# v1.net
KiCad netlist of a schematic drawn in EAGLE
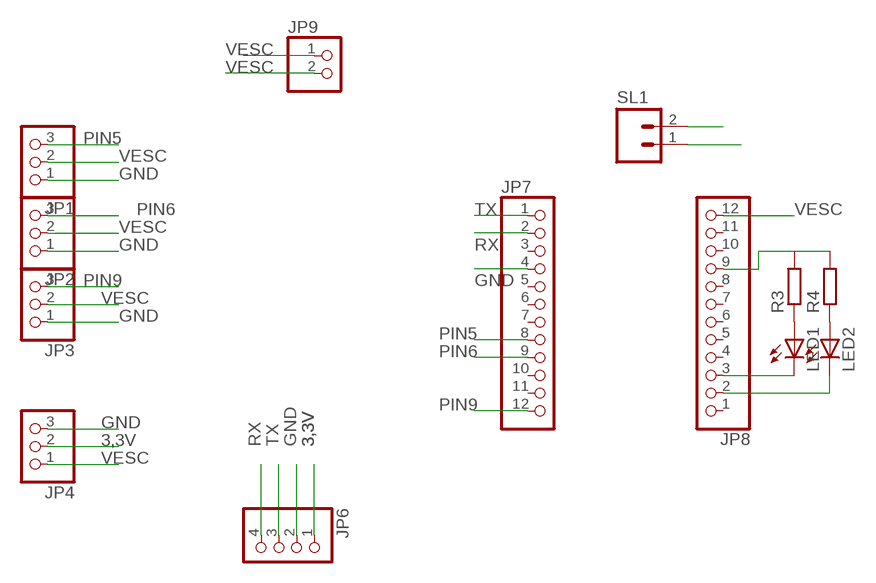
[diagram p0: schematic, sheet 1]

(export (version "E")
  (design (tool "Eeschema 10.0.6"))
  (components
    (comp (ref "JP1")
      (value "PINHD-1X3")
      (footprint "eagle-import:1X03")
      (libsource (lib "eagle-import") (part "PINHD-1X3"))
    )
    (comp (ref "JP2")
      (value "PINHD-1X3")
      (footprint "eagle-import:1X03")
      (libsource (lib "eagle-import") (part "PINHD-1X3"))
    )
    (comp (ref "JP3")
      (value "PINHD-1X3")
      (footprint "eagle-import:1X03")
      (libsource (lib "eagle-import") (part "PINHD-1X3"))
    )
    (comp (ref "JP4")
      (value "PINHD-1X3")
      (footprint "eagle-import:1X03")
      (libsource (lib "eagle-import") (part "PINHD-1X3"))
    )
    (comp (ref "JP6")
      (value "PINHD-1X4")
      (footprint "eagle-import:1X04")
      (libsource (lib "eagle-import") (part "PINHD-1X4"))
    )
    (comp (ref "JP7")
      (value "PINHD-1X12")
      (footprint "eagle-import:1X12")
      (libsource (lib "eagle-import") (part "PINHD-1X12"))
    )
    (comp (ref "JP8")
      (value "PINHD-1X12")
      (footprint "eagle-import:1X12")
      (libsource (lib "eagle-import") (part "PINHD-1X12"))
    )
    (comp (ref "JP9")
      (value "PINHD-1X2")
      (footprint "eagle-import:1X02")
      (libsource (lib "eagle-import") (part "PINHD-1X2"))
    )
    (comp (ref "LED1")
      (value "LED3MM")
      (footprint "eagle-import:LED3MM")
      (libsource (lib "eagle-import") (part "LED3MM"))
    )
    (comp (ref "LED2")
      (value "LED3MM")
      (footprint "eagle-import:LED3MM")
      (libsource (lib "eagle-import") (part "LED3MM"))
    )
    (comp (ref "R3")
      (value "R-EU_0207/7")
      (footprint "eagle-import:0207_7")
      (libsource (lib "eagle-import") (part "R-EU_0207/7"))
    )
    (comp (ref "R4")
      (value "R-EU_0207/7")
      (footprint "eagle-import:0207_7")
      (libsource (lib "eagle-import") (part "R-EU_0207/7"))
    )
    (comp (ref "SL1")
      (value "M02")
      (footprint "eagle-import:02P")
      (libsource (lib "eagle-import") (part "M02"))
    )
  )
  (nets
    (net (code "1") (name "/3,3V") (class "Default")
      (node (ref "JP4") (pin "2") (pinfunction "2_2") (pintype "passive"))
      (node (ref "JP6") (pin "1") (pinfunction "1_1") (pintype "passive"))
    )
    (net (code "2") (name "/GND") (class "Default")
      (node (ref "JP1") (pin "1") (pinfunction "1_1") (pintype "passive"))
      (node (ref "JP2") (pin "1") (pinfunction "1_1") (pintype "passive"))
      (node (ref "JP3") (pin "1") (pinfunction "1_1") (pintype "passive"))
      (node (ref "JP4") (pin "3") (pinfunction "3_3") (pintype "passive"))
      (node (ref "JP6") (pin "2") (pinfunction "2_2") (pintype "passive"))
      (node (ref "JP7") (pin "4") (pinfunction "4_4") (pintype "passive"))
      (node (ref "SL1") (pin "2") (pinfunction "2_2") (pintype "passive"))
    )
    (net (code "3") (name "/PIN5") (class "Default")
      (node (ref "JP1") (pin "3") (pinfunction "3_3") (pintype "passive"))
      (node (ref "JP7") (pin "8") (pinfunction "8_8") (pintype "passive"))
    )
    (net (code "4") (name "/PIN6") (class "Default")
      (node (ref "JP2") (pin "3") (pinfunction "3_3") (pintype "passive"))
      (node (ref "JP7") (pin "9") (pinfunction "9_9") (pintype "passive"))
    )
    (net (code "5") (name "/PIN9") (class "Default")
      (node (ref "JP3") (pin "3") (pinfunction "3_3") (pintype "passive"))
      (node (ref "JP7") (pin "12") (pinfunction "12_12") (pintype "passive"))
    )
    (net (code "6") (name "/RX") (class "Default")
      (node (ref "JP6") (pin "4") (pinfunction "4_4") (pintype "passive"))
      (node (ref "JP7") (pin "2") (pinfunction "2_2") (pintype "passive"))
    )
    (net (code "7") (name "/TX") (class "Default")
      (node (ref "JP6") (pin "3") (pinfunction "3_3") (pintype "passive"))
      (node (ref "JP7") (pin "1") (pinfunction "1_1") (pintype "passive"))
    )
    (net (code "8") (name "/VESC") (class "Default")
      (node (ref "JP1") (pin "2") (pinfunction "2_2") (pintype "passive"))
      (node (ref "JP2") (pin "2") (pinfunction "2_2") (pintype "passive"))
      (node (ref "JP3") (pin "2") (pinfunction "2_2") (pintype "passive"))
      (node (ref "JP4") (pin "1") (pinfunction "1_1") (pintype "passive"))
      (node (ref "JP8") (pin "12") (pinfunction "12_12") (pintype "passive"))
      (node (ref "JP9") (pin "1") (pinfunction "1_1") (pintype "passive"))
      (node (ref "JP9") (pin "2") (pinfunction "2_2") (pintype "passive"))
      (node (ref "SL1") (pin "1") (pinfunction "1_1") (pintype "passive"))
    )
    (net (code "9") (name "Net-(JP8-Pad9)") (class "Default")
      (node (ref "JP8") (pin "9") (pinfunction "9_9") (pintype "passive"))
      (node (ref "R3") (pin "2") (pinfunction "2_2") (pintype "passive"))
      (node (ref "R4") (pin "2") (pinfunction "2_2") (pintype "passive"))
    )
    (net (code "10") (name "Net-(LED1-C)") (class "Default")
      (node (ref "JP8") (pin "3") (pinfunction "3_3") (pintype "passive"))
      (node (ref "LED1") (pin "K") (pinfunction "C_K") (pintype "passive"))
    )
    (net (code "11") (name "Net-(LED1-PadA)") (class "Default")
      (node (ref "LED1") (pin "A") (pinfunction "A_A") (pintype "passive"))
      (node (ref "R3") (pin "1") (pinfunction "1_1") (pintype "passive"))
    )
    (net (code "12") (name "Net-(LED2-C)") (class "Default")
      (node (ref "JP8") (pin "2") (pinfunction "2_2") (pintype "passive"))
      (node (ref "LED2") (pin "K") (pinfunction "C_K") (pintype "passive"))
    )
    (net (code "13") (name "Net-(LED2-PadA)") (class "Default")
      (node (ref "LED2") (pin "A") (pinfunction "A_A") (pintype "passive"))
      (node (ref "R4") (pin "1") (pinfunction "1_1") (pintype "passive"))
    )
    (net (code "14") (name "unconnected-(JP7-Pad3)") (class "Default")
      (node (ref "JP7") (pin "3") (pinfunction "3_3") (pintype "passive"))
    )
    (net (code "15") (name "unconnected-(JP7-Pad5)") (class "Default")
      (node (ref "JP7") (pin "5") (pinfunction "5_5") (pintype "passive"))
    )
    (net (code "16") (name "unconnected-(JP7-Pad6)") (class "Default")
      (node (ref "JP7") (pin "6") (pinfunction "6_6") (pintype "passive"))
    )
    (net (code "17") (name "unconnected-(JP7-Pad7)") (class "Default")
      (node (ref "JP7") (pin "7") (pinfunction "7_7") (pintype "passive"))
    )
    (net (code "18") (name "unconnected-(JP7-Pad10)") (class "Default")
      (node (ref "JP7") (pin "10") (pinfunction "10_10") (pintype "passive"))
    )
    (net (code "19") (name "unconnected-(JP7-Pad11)") (class "Default")
      (node (ref "JP7") (pin "11") (pinfunction "11_11") (pintype "passive"))
    )
    (net (code "20") (name "unconnected-(JP8-Pad1)") (class "Default")
      (node (ref "JP8") (pin "1") (pinfunction "1_1") (pintype "passive"))
    )
    (net (code "21") (name "unconnected-(JP8-Pad4)") (class "Default")
      (node (ref "JP8") (pin "4") (pinfunction "4_4") (pintype "passive"))
    )
    (net (code "22") (name "unconnected-(JP8-Pad5)") (class "Default")
      (node (ref "JP8") (pin "5") (pinfunction "5_5") (pintype "passive"))
    )
    (net (code "23") (name "unconnected-(JP8-Pad6)") (class "Default")
      (node (ref "JP8") (pin "6") (pinfunction "6_6") (pintype "passive"))
    )
    (net (code "24") (name "unconnected-(JP8-Pad7)") (class "Default")
      (node (ref "JP8") (pin "7") (pinfunction "7_7") (pintype "passive"))
    )
    (net (code "25") (name "unconnected-(JP8-Pad8)") (class "Default")
      (node (ref "JP8") (pin "8") (pinfunction "8_8") (pintype "passive"))
    )
    (net (code "26") (name "unconnected-(JP8-Pad10)") (class "Default")
      (node (ref "JP8") (pin "10") (pinfunction "10_10") (pintype "passive"))
    )
    (net (code "27") (name "unconnected-(JP8-Pad11)") (class "Default")
      (node (ref "JP8") (pin "11") (pinfunction "11_11") (pintype "passive"))
    )
  )
)
